# controller_A-rev_1.net
KiCad netlist of a schematic drawn in EAGLE
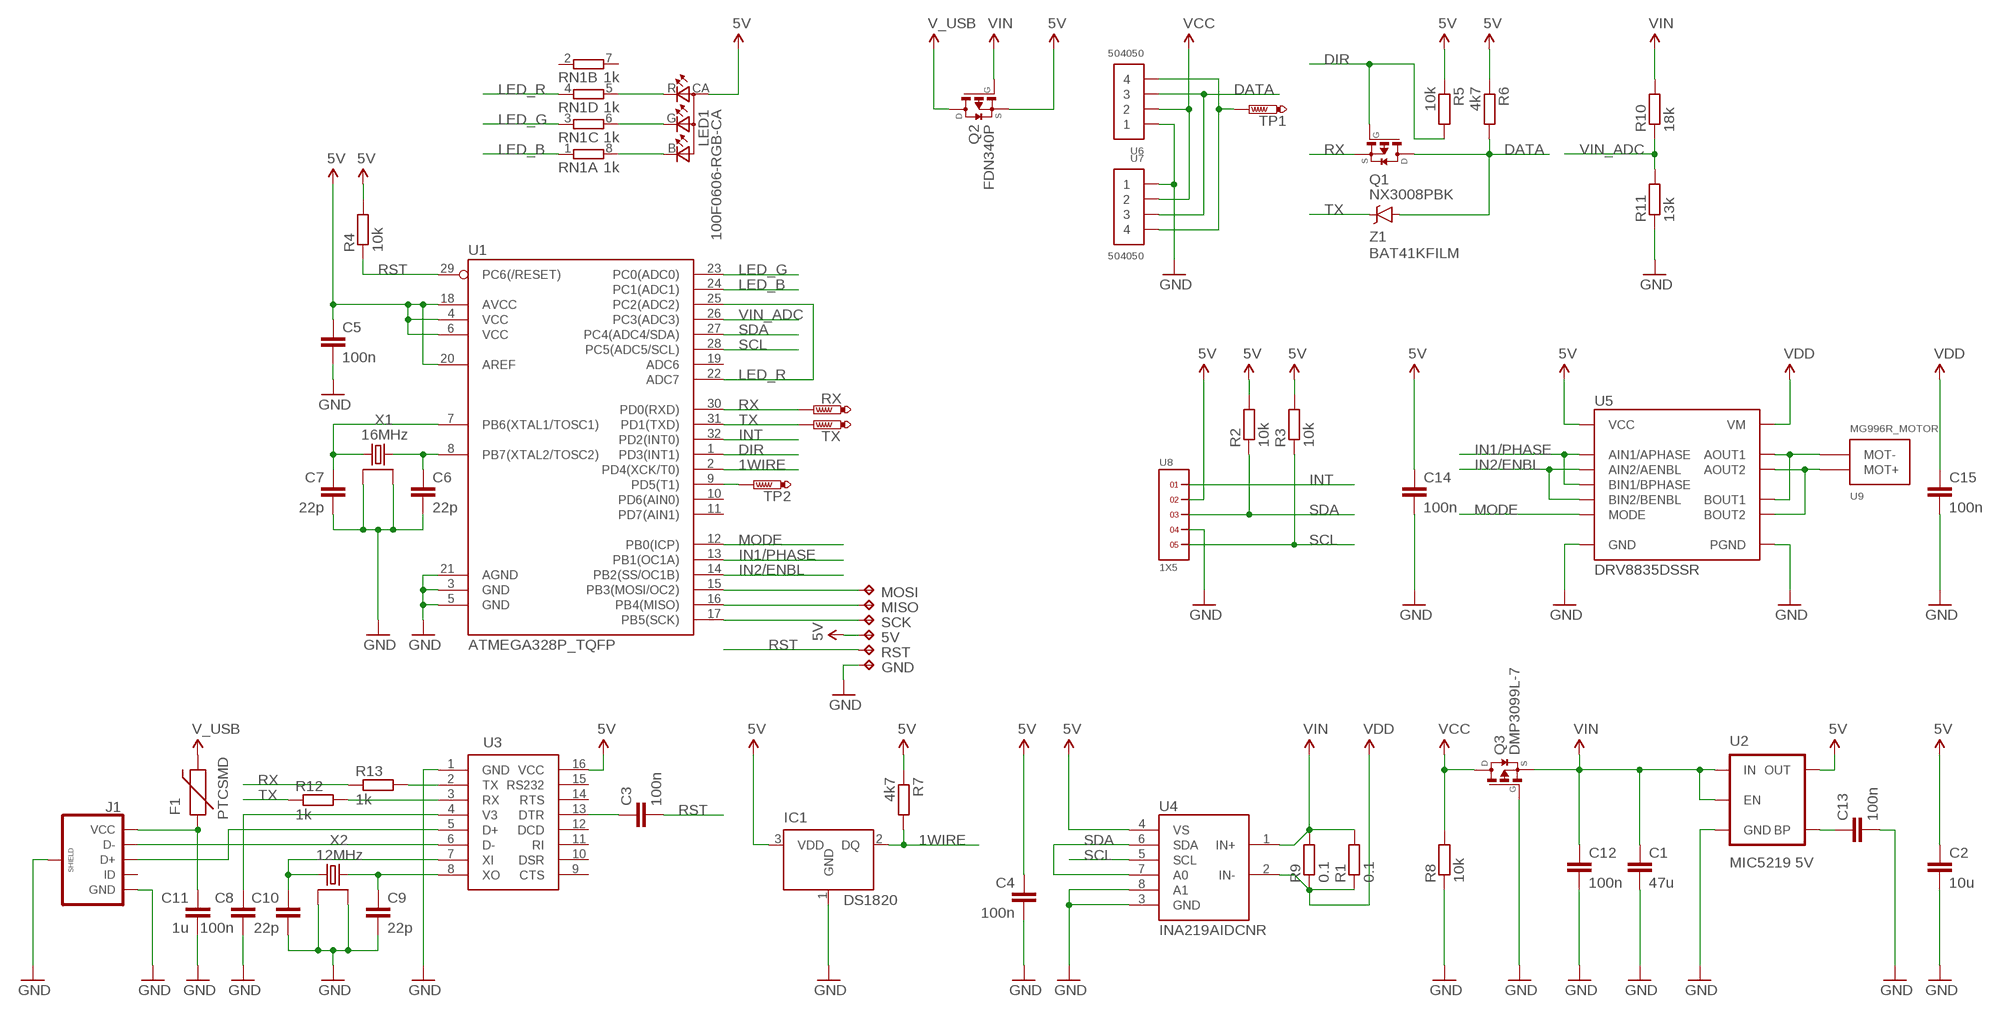
[diagram p0: schematic, sheet 1]

(export (version "E")
  (design (tool "Eeschema 10.0.6"))
  (components
    (comp (ref "5V")
      (value "TPTP07SQ")
      (footprint "eagle-import:TP07SQ")
      (libsource (lib "eagle-import") (part "TPTP07SQ"))
    )
    (comp (ref "C1")
      (value "47u")
      (footprint "eagle-import:C1206")
      (libsource (lib "eagle-import") (part "C-EUC1206"))
    )
    (comp (ref "C2")
      (value "10u")
      (footprint "eagle-import:C0603K")
      (libsource (lib "eagle-import") (part "C-EUC0603K"))
    )
    (comp (ref "C3")
      (value "100n")
      (footprint "eagle-import:C0402K")
      (libsource (lib "eagle-import") (part "C-EUC0402K"))
    )
    (comp (ref "C4")
      (value "100n")
      (footprint "eagle-import:C0402K")
      (libsource (lib "eagle-import") (part "C-EUC0402K"))
    )
    (comp (ref "C5")
      (value "100n")
      (footprint "eagle-import:C0402K")
      (libsource (lib "eagle-import") (part "C-EUC0402K"))
    )
    (comp (ref "C6")
      (value "22p")
      (footprint "eagle-import:C0402K")
      (libsource (lib "eagle-import") (part "C-EUC0402K"))
    )
    (comp (ref "C7")
      (value "22p")
      (footprint "eagle-import:C0402K")
      (libsource (lib "eagle-import") (part "C-EUC0402K"))
    )
    (comp (ref "C8")
      (value "100n")
      (footprint "eagle-import:C0402K")
      (libsource (lib "eagle-import") (part "C-EUC0402K"))
    )
    (comp (ref "C9")
      (value "22p")
      (footprint "eagle-import:C0402K")
      (libsource (lib "eagle-import") (part "C-EUC0402K"))
    )
    (comp (ref "C10")
      (value "22p")
      (footprint "eagle-import:C0402K")
      (libsource (lib "eagle-import") (part "C-EUC0402K"))
    )
    (comp (ref "C11")
      (value "1u")
      (footprint "eagle-import:C0402K")
      (libsource (lib "eagle-import") (part "C-EUC0402K"))
    )
    (comp (ref "C12")
      (value "100n")
      (footprint "eagle-import:C0402K")
      (libsource (lib "eagle-import") (part "C-EUC0402K"))
    )
    (comp (ref "C13")
      (value "100n")
      (footprint "eagle-import:C0402K")
      (libsource (lib "eagle-import") (part "C-EUC0402K"))
    )
    (comp (ref "C14")
      (value "100n")
      (footprint "eagle-import:C0402K")
      (libsource (lib "eagle-import") (part "C-EUC0402K"))
    )
    (comp (ref "C15")
      (value "100n")
      (footprint "eagle-import:C0402K")
      (libsource (lib "eagle-import") (part "C-EUC0402K"))
    )
    (comp (ref "F1")
      (value "PTCSMD")
      (footprint "eagle-import:PTC-1206")
      (libsource (lib "eagle-import") (part "PTCSMD"))
    )
    (comp (ref "GND")
      (value "TPTP07SQ")
      (footprint "eagle-import:TP07SQ")
      (libsource (lib "eagle-import") (part "TPTP07SQ"))
    )
    (comp (ref "IC1")
      (value "DS1820")
      (footprint "eagle-import:TO-92")
      (libsource (lib "eagle-import") (part "DS1820"))
    )
    (comp (ref "J1")
      (value "USB_MICROB_PLUGCONN-11752")
      (footprint "eagle-import:USB-B-MICRO-SMD_V03")
      (libsource (lib "eagle-import") (part "USB_MICROB_PLUGCONN-11752"))
    )
    (comp (ref "LED1")
      (value "100F0606-RGB-CA")
      (footprint "eagle-import:1616")
      (libsource (lib "eagle-import") (part "100F0606-RGB-CA"))
    )
    (comp (ref "MISO")
      (value "TPTP07SQ")
      (footprint "eagle-import:TP07SQ")
      (libsource (lib "eagle-import") (part "TPTP07SQ"))
    )
    (comp (ref "MOSI")
      (value "TPTP07SQ")
      (footprint "eagle-import:TP07SQ")
      (libsource (lib "eagle-import") (part "TPTP07SQ"))
    )
    (comp (ref "Q1")
      (value "NX3008PBK")
      (footprint "eagle-import:SSOT-3")
      (libsource (lib "eagle-import") (part "FDN340P"))
    )
    (comp (ref "Q2")
      (value "FDN340P")
      (footprint "eagle-import:SSOT-3")
      (libsource (lib "eagle-import") (part "FDN340P"))
    )
    (comp (ref "Q3")
      (value "DMP3099L-7")
      (footprint "eagle-import:SOT23")
      (libsource (lib "eagle-import") (part "SI2333DS"))
    )
    (comp (ref "R1")
      (value "0.1")
      (footprint "eagle-import:R0603")
      (libsource (lib "eagle-import") (part "R-EU_R0603"))
    )
    (comp (ref "R2")
      (value "10k")
      (footprint "eagle-import:R0402")
      (libsource (lib "eagle-import") (part "R-EU_R0402"))
    )
    (comp (ref "R3")
      (value "10k")
      (footprint "eagle-import:R0402")
      (libsource (lib "eagle-import") (part "R-EU_R0402"))
    )
    (comp (ref "R4")
      (value "10k")
      (footprint "eagle-import:R0402")
      (libsource (lib "eagle-import") (part "R-EU_R0402"))
    )
    (comp (ref "R5")
      (value "10k")
      (footprint "eagle-import:R0402")
      (libsource (lib "eagle-import") (part "R-EU_R0402"))
    )
    (comp (ref "R6")
      (value "4k7")
      (footprint "eagle-import:R0402")
      (libsource (lib "eagle-import") (part "R-EU_R0402"))
    )
    (comp (ref "R7")
      (value "4k7")
      (footprint "eagle-import:R0402")
      (libsource (lib "eagle-import") (part "R-EU_R0402"))
    )
    (comp (ref "R8")
      (value "10k")
      (footprint "eagle-import:R0402")
      (libsource (lib "eagle-import") (part "R-EU_R0402"))
    )
    (comp (ref "R9")
      (value "0.1")
      (footprint "eagle-import:R2512")
      (libsource (lib "eagle-import") (part "R-EU_R2512"))
    )
    (comp (ref "R10")
      (value "18k")
      (footprint "eagle-import:R0402")
      (libsource (lib "eagle-import") (part "R-EU_R0402"))
    )
    (comp (ref "R11")
      (value "13k")
      (footprint "eagle-import:R0402")
      (libsource (lib "eagle-import") (part "R-EU_R0402"))
    )
    (comp (ref "R12")
      (value "1k")
      (footprint "eagle-import:R0402")
      (libsource (lib "eagle-import") (part "R-EU_R0402"))
    )
    (comp (ref "R13")
      (value "1k")
      (footprint "eagle-import:R0402")
      (libsource (lib "eagle-import") (part "R-EU_R0402"))
    )
    (comp (ref "RN1")
      (value "1k")
      (footprint "eagle-import:YC124")
      (libsource (lib "eagle-import") (part "4R-NYC124"))
    )
    (comp (ref "RST")
      (value "TPTP07SQ")
      (footprint "eagle-import:TP07SQ")
      (libsource (lib "eagle-import") (part "TPTP07SQ"))
    )
    (comp (ref "RX")
      (value "PTR1TP10R")
      (footprint "eagle-import:TP10R")
      (libsource (lib "eagle-import") (part "PTR1TP10R"))
    )
    (comp (ref "SCK")
      (value "TPTP07SQ")
      (footprint "eagle-import:TP07SQ")
      (libsource (lib "eagle-import") (part "TPTP07SQ"))
    )
    (comp (ref "TP1")
      (value "PTR1TP10R")
      (footprint "eagle-import:TP10R")
      (libsource (lib "eagle-import") (part "PTR1TP10R"))
    )
    (comp (ref "TP2")
      (value "PTR1TP10R")
      (footprint "eagle-import:TP10R")
      (libsource (lib "eagle-import") (part "PTR1TP10R"))
    )
    (comp (ref "TX")
      (value "PTR1TP10R")
      (footprint "eagle-import:TP10R")
      (libsource (lib "eagle-import") (part "PTR1TP10R"))
    )
    (comp (ref "U1")
      (value "ATMEGA328P_TQFP")
      (footprint "eagle-import:TQFP32-08")
      (libsource (lib "eagle-import") (part "ATMEGA328P_TQFP"))
    )
    (comp (ref "U2")
      (value "MIC5219 5V")
      (footprint "eagle-import:SOT23-5")
      (libsource (lib "eagle-import") (part "V_REG_MIC52195V"))
    )
    (comp (ref "U3")
      (value "CH340G")
      (footprint "eagle-import:SOIC16")
      (libsource (lib "eagle-import") (part "CH340G"))
    )
    (comp (ref "U4")
      (value "INA219AIDCNR")
      (footprint "eagle-import:SOT23-8L")
      (libsource (lib "eagle-import") (part "INA219AIDCNR"))
    )
    (comp (ref "U5")
      (value "DRV8835DSSR")
      (footprint "eagle-import:WSON-12")
      (libsource (lib "eagle-import") (part "DRV8835DSSR"))
    )
    (comp (ref "U6")
      (value "504050")
      (footprint "eagle-import:504050")
      (libsource (lib "eagle-import") (part "504050"))
    )
    (comp (ref "U7")
      (value "504050")
      (footprint "eagle-import:504050")
      (libsource (lib "eagle-import") (part "504050"))
    )
    (comp (ref "U8")
      (value "1X5")
      (footprint "eagle-import:1X5")
      (libsource (lib "eagle-import") (part "1X5"))
    )
    (comp (ref "U9")
      (value "MG996R_MOTOR")
      (footprint "eagle-import:MOTOR")
      (libsource (lib "eagle-import") (part "MG996R_MOTOR"))
    )
    (comp (ref "X1")
      (value "16MHz")
      (footprint "eagle-import:OSC3225")
      (libsource (lib "eagle-import") (part "GSX-331"))
    )
    (comp (ref "X2")
      (value "12MHz")
      (footprint "eagle-import:OSC3225")
      (libsource (lib "eagle-import") (part "GSX-331"))
    )
    (comp (ref "Z1")
      (value "BAT41KFILM")
      (footprint "eagle-import:SOD-523")
      (libsource (lib "eagle-import") (part "BAT41KFILM"))
    )
  )
  (nets
    (net (code "1") (name "/1WIRE") (class "Default")
      (node (ref "IC1") (pin "2") (pinfunction "DQ_2") (pintype "output"))
      (node (ref "R7") (pin "2") (pinfunction "2_2") (pintype "passive"))
      (node (ref "U1") (pin "2") (pinfunction "PD4(XCK/T0)_2") (pintype "bidirectional"))
    )
    (net (code "2") (name "/DATA") (class "Default")
      (node (ref "Q1") (pin "3") (pinfunction "D_3") (pintype "passive"))
      (node (ref "R6") (pin "2") (pinfunction "2_2") (pintype "passive"))
      (node (ref "U6") (pin "P$3") (pinfunction "3_P$3") (pintype "bidirectional"))
      (node (ref "U7") (pin "P$3") (pinfunction "3_P$3") (pintype "bidirectional"))
      (node (ref "Z1") (pin "P$1") (pinfunction "1_P$1") (pintype "passive"))
    )
    (net (code "3") (name "/DIR") (class "Default")
      (node (ref "Q1") (pin "1") (pinfunction "G_1") (pintype "passive"))
      (node (ref "R5") (pin "2") (pinfunction "2_2") (pintype "passive"))
      (node (ref "U1") (pin "1") (pinfunction "PD3(INT1)_1") (pintype "bidirectional"))
    )
    (net (code "4") (name "/IN1{slash}PHASE") (class "Default")
      (node (ref "U1") (pin "13") (pinfunction "PB1(OC1A)_13") (pintype "bidirectional"))
      (node (ref "U5") (pin "P$10") (pinfunction "AIN1/APHASE_P$10") (pintype "bidirectional"))
      (node (ref "U5") (pin "P$8") (pinfunction "BIN1/BPHASE_P$8") (pintype "bidirectional"))
    )
    (net (code "5") (name "/IN2{slash}ENBL") (class "Default")
      (node (ref "U1") (pin "14") (pinfunction "PB2(SS/OC1B)_14") (pintype "bidirectional"))
      (node (ref "U5") (pin "P$7") (pinfunction "BIN2/BENBL_P$7") (pintype "bidirectional"))
      (node (ref "U5") (pin "P$9") (pinfunction "AIN2/AENBL_P$9") (pintype "bidirectional"))
    )
    (net (code "6") (name "/INT") (class "Default")
      (node (ref "U1") (pin "32") (pinfunction "PD2(INT0)_32") (pintype "bidirectional"))
      (node (ref "U8") (pin "1") (pinfunction "1_1") (pintype "bidirectional"))
    )
    (net (code "7") (name "/LED_B") (class "Default")
      (node (ref "RN1") (pin "1") (pinfunction "1_1") (pintype "passive"))
      (node (ref "U1") (pin "24") (pinfunction "PC1(ADC1)_24") (pintype "bidirectional"))
    )
    (net (code "8") (name "/LED_G") (class "Default")
      (node (ref "RN1") (pin "3") (pinfunction "1_3") (pintype "passive"))
      (node (ref "U1") (pin "23") (pinfunction "PC0(ADC0)_23") (pintype "bidirectional"))
    )
    (net (code "9") (name "/LED_R") (class "Default")
      (node (ref "RN1") (pin "4") (pinfunction "1_4") (pintype "passive"))
      (node (ref "U1") (pin "22") (pinfunction "ADC7_22") (pintype "bidirectional"))
      (node (ref "U1") (pin "25") (pinfunction "PC2(ADC2)_25") (pintype "bidirectional"))
    )
    (net (code "10") (name "/MODE") (class "Default")
      (node (ref "U1") (pin "12") (pinfunction "PB0(ICP)_12") (pintype "bidirectional"))
      (node (ref "U5") (pin "P$11") (pinfunction "MODE_P$11") (pintype "bidirectional"))
    )
    (net (code "11") (name "/RST") (class "Default")
      (node (ref "C3") (pin "2") (pinfunction "2_2") (pintype "passive"))
      (node (ref "R4") (pin "1") (pinfunction "1_1") (pintype "passive"))
      (node (ref "RST") (pin "TP") (pinfunction "TP_TP") (pintype "input"))
      (node (ref "U1") (pin "29") (pinfunction "PC6(/RESET)_29") (pintype "bidirectional"))
    )
    (net (code "12") (name "/RX") (class "Default")
      (node (ref "Q1") (pin "2") (pinfunction "S_2") (pintype "passive"))
      (node (ref "R13") (pin "1") (pinfunction "1_1") (pintype "passive"))
      (node (ref "RX") (pin "TP") (pinfunction "TP_TP") (pintype "input"))
      (node (ref "U1") (pin "30") (pinfunction "PD0(RXD)_30") (pintype "bidirectional"))
    )
    (net (code "13") (name "/SCL") (class "Default")
      (node (ref "R3") (pin "1") (pinfunction "1_1") (pintype "passive"))
      (node (ref "U1") (pin "28") (pinfunction "PC5(ADC5/SCL)_28") (pintype "bidirectional"))
      (node (ref "U4") (pin "5") (pinfunction "SCL_5") (pintype "bidirectional"))
      (node (ref "U8") (pin "5") (pinfunction "5_5") (pintype "bidirectional"))
    )
    (net (code "14") (name "/SDA") (class "Default")
      (node (ref "R2") (pin "1") (pinfunction "1_1") (pintype "passive"))
      (node (ref "U1") (pin "27") (pinfunction "PC4(ADC4/SDA)_27") (pintype "bidirectional"))
      (node (ref "U4") (pin "6") (pinfunction "SDA_6") (pintype "bidirectional"))
      (node (ref "U4") (pin "7") (pinfunction "A0_7") (pintype "input"))
      (node (ref "U8") (pin "3") (pinfunction "3_3") (pintype "bidirectional"))
    )
    (net (code "15") (name "/TX") (class "Default")
      (node (ref "R12") (pin "1") (pinfunction "1_1") (pintype "passive"))
      (node (ref "TX") (pin "TP") (pinfunction "TP_TP") (pintype "input"))
      (node (ref "U1") (pin "31") (pinfunction "PD1(TXD)_31") (pintype "bidirectional"))
      (node (ref "Z1") (pin "P$2") (pinfunction "2_P$2") (pintype "passive"))
    )
    (net (code "16") (name "/VIN_ADC") (class "Default")
      (node (ref "R10") (pin "1") (pinfunction "1_1") (pintype "passive"))
      (node (ref "R11") (pin "2") (pinfunction "2_2") (pintype "passive"))
      (node (ref "U1") (pin "26") (pinfunction "PC3(ADC3)_26") (pintype "bidirectional"))
    )
    (net (code "17") (name "5V") (class "Default")
      (node (ref "5V") (pin "TP") (pinfunction "TP_TP") (pintype "input"))
      (node (ref "C14") (pin "1") (pinfunction "1_1") (pintype "passive"))
      (node (ref "C2") (pin "1") (pinfunction "1_1") (pintype "passive"))
      (node (ref "C4") (pin "1") (pinfunction "1_1") (pintype "passive"))
      (node (ref "C5") (pin "1") (pinfunction "1_1") (pintype "passive"))
      (node (ref "IC1") (pin "3") (pinfunction "VDD_3") (pintype "input"))
      (node (ref "LED1") (pin "CA") (pinfunction "CA_CA") (pintype "passive"))
      (node (ref "Q2") (pin "2") (pinfunction "S_2") (pintype "passive"))
      (node (ref "R2") (pin "2") (pinfunction "2_2") (pintype "passive"))
      (node (ref "R3") (pin "2") (pinfunction "2_2") (pintype "passive"))
      (node (ref "R4") (pin "2") (pinfunction "2_2") (pintype "passive"))
      (node (ref "R5") (pin "1") (pinfunction "1_1") (pintype "passive"))
      (node (ref "R6") (pin "1") (pinfunction "1_1") (pintype "passive"))
      (node (ref "R7") (pin "1") (pinfunction "1_1") (pintype "passive"))
      (node (ref "U1") (pin "18") (pinfunction "AVCC_18") (pintype "bidirectional"))
      (node (ref "U1") (pin "20") (pinfunction "AREF_20") (pintype "bidirectional"))
      (node (ref "U1") (pin "4") (pinfunction "VCC_4") (pintype "bidirectional"))
      (node (ref "U1") (pin "6") (pinfunction "VCC_6") (pintype "bidirectional"))
      (node (ref "U2") (pin "5") (pinfunction "OUT_5") (pintype "passive"))
      (node (ref "U3") (pin "16") (pinfunction "VCC_16") (pintype "bidirectional"))
      (node (ref "U4") (pin "4") (pinfunction "VS_4") (pintype "power_in"))
      (node (ref "U5") (pin "P$12") (pinfunction "VCC_P$12") (pintype "bidirectional"))
      (node (ref "U8") (pin "2") (pinfunction "2_2") (pintype "bidirectional"))
    )
    (net (code "18") (name "GND") (class "Default")
      (node (ref "C1") (pin "2") (pinfunction "2_2") (pintype "passive"))
      (node (ref "C10") (pin "2") (pinfunction "2_2") (pintype "passive"))
      (node (ref "C11") (pin "2") (pinfunction "2_2") (pintype "passive"))
      (node (ref "C12") (pin "2") (pinfunction "2_2") (pintype "passive"))
      (node (ref "C13") (pin "2") (pinfunction "2_2") (pintype "passive"))
      (node (ref "C14") (pin "2") (pinfunction "2_2") (pintype "passive"))
      (node (ref "C15") (pin "2") (pinfunction "2_2") (pintype "passive"))
      (node (ref "C2") (pin "2") (pinfunction "2_2") (pintype "passive"))
      (node (ref "C4") (pin "2") (pinfunction "2_2") (pintype "passive"))
      (node (ref "C5") (pin "2") (pinfunction "2_2") (pintype "passive"))
      (node (ref "C6") (pin "2") (pinfunction "2_2") (pintype "passive"))
      (node (ref "C7") (pin "2") (pinfunction "2_2") (pintype "passive"))
      (node (ref "C8") (pin "2") (pinfunction "2_2") (pintype "passive"))
      (node (ref "C9") (pin "2") (pinfunction "2_2") (pintype "passive"))
      (node (ref "GND") (pin "TP") (pinfunction "TP_TP") (pintype "input"))
      (node (ref "IC1") (pin "1") (pinfunction "GND_1") (pintype "power_in"))
      (node (ref "J1") (pin "GND") (pinfunction "GND_GND") (pintype "bidirectional"))
      (node (ref "J1") (pin "SHIELD1") (pinfunction "SHIELD_SHIELD1") (pintype "bidirectional"))
      (node (ref "J1") (pin "SHIELD2") (pinfunction "SHIELD_SHIELD2") (pintype "bidirectional"))
      (node (ref "J1") (pin "SHIELD3") (pinfunction "SHIELD_SHIELD3") (pintype "bidirectional"))
      (node (ref "Q3") (pin "1") (pinfunction "G_1") (pintype "passive"))
      (node (ref "R11") (pin "1") (pinfunction "1_1") (pintype "passive"))
      (node (ref "R8") (pin "1") (pinfunction "1_1") (pintype "passive"))
      (node (ref "U1") (pin "21") (pinfunction "AGND_21") (pintype "bidirectional"))
      (node (ref "U1") (pin "3") (pinfunction "GND_3") (pintype "bidirectional"))
      (node (ref "U1") (pin "5") (pinfunction "GND_5") (pintype "bidirectional"))
      (node (ref "U2") (pin "2") (pinfunction "GND_2") (pintype "input"))
      (node (ref "U3") (pin "1") (pinfunction "GND_1") (pintype "bidirectional"))
      (node (ref "U4") (pin "3") (pinfunction "GND_3") (pintype "power_in"))
      (node (ref "U4") (pin "8") (pinfunction "A1_8") (pintype "input"))
      (node (ref "U5") (pin "P$13") (pinfunction "PGND_P$13") (pintype "bidirectional"))
      (node (ref "U5") (pin "P$14") (pinfunction "PGND_P$14") (pintype "bidirectional"))
      (node (ref "U5") (pin "P$15") (pinfunction "PGND_P$15") (pintype "bidirectional"))
      (node (ref "U5") (pin "P$16") (pinfunction "PGND_P$16") (pintype "bidirectional"))
      (node (ref "U5") (pin "P$6") (pinfunction "GND_P$6") (pintype "bidirectional"))
      (node (ref "U6") (pin "P$1") (pinfunction "1_P$1") (pintype "bidirectional"))
      (node (ref "U7") (pin "P$1") (pinfunction "1_P$1") (pintype "bidirectional"))
      (node (ref "U8") (pin "4") (pinfunction "4_4") (pintype "bidirectional"))
      (node (ref "X1") (pin "P$2") (pinfunction "2_P$2") (pintype "passive"))
      (node (ref "X1") (pin "P$4") (pinfunction "4_P$4") (pintype "passive"))
      (node (ref "X2") (pin "P$2") (pinfunction "2_P$2") (pintype "passive"))
      (node (ref "X2") (pin "P$4") (pinfunction "4_P$4") (pintype "passive"))
    )
    (net (code "19") (name "Net-(J1-VCC)") (class "Default")
      (node (ref "C11") (pin "1") (pinfunction "1_1") (pintype "passive"))
      (node (ref "F1") (pin "1") (pinfunction "1_1") (pintype "bidirectional"))
      (node (ref "J1") (pin "VBUS") (pinfunction "VCC_VBUS") (pintype "bidirectional"))
    )
    (net (code "20") (name "Net-(RN1A-2)") (class "Default")
      (node (ref "LED1") (pin "B") (pinfunction "B_B") (pintype "passive"))
      (node (ref "RN1") (pin "8") (pinfunction "2_8") (pintype "passive"))
    )
    (net (code "21") (name "Net-(RN1C-2)") (class "Default")
      (node (ref "LED1") (pin "G") (pinfunction "G_G") (pintype "passive"))
      (node (ref "RN1") (pin "6") (pinfunction "2_6") (pintype "passive"))
    )
    (net (code "22") (name "Net-(RN1D-2)") (class "Default")
      (node (ref "LED1") (pin "R") (pinfunction "R_R") (pintype "passive"))
      (node (ref "RN1") (pin "5") (pinfunction "2_5") (pintype "passive"))
    )
    (net (code "23") (name "Net-(U1-PB3(MOSI{slash}OC2))") (class "Default")
      (node (ref "MOSI") (pin "TP") (pinfunction "TP_TP") (pintype "input"))
      (node (ref "U1") (pin "15") (pinfunction "PB3(MOSI/OC2)_15") (pintype "bidirectional"))
    )
    (net (code "24") (name "Net-(U1-PB4(MISO))") (class "Default")
      (node (ref "MISO") (pin "TP") (pinfunction "TP_TP") (pintype "input"))
      (node (ref "U1") (pin "16") (pinfunction "PB4(MISO)_16") (pintype "bidirectional"))
    )
    (net (code "25") (name "Net-(U1-PB5(SCK))") (class "Default")
      (node (ref "SCK") (pin "TP") (pinfunction "TP_TP") (pintype "input"))
      (node (ref "U1") (pin "17") (pinfunction "PB5(SCK)_17") (pintype "bidirectional"))
    )
    (net (code "26") (name "Net-(U1-PB6(XTAL1{slash}TOSC1))") (class "Default")
      (node (ref "C7") (pin "1") (pinfunction "1_1") (pintype "passive"))
      (node (ref "U1") (pin "7") (pinfunction "PB6(XTAL1/TOSC1)_7") (pintype "bidirectional"))
      (node (ref "X1") (pin "P$3") (pinfunction "3_P$3") (pintype "passive"))
    )
    (net (code "27") (name "Net-(U1-PB7(XTAL2{slash}TOSC2))") (class "Default")
      (node (ref "C6") (pin "1") (pinfunction "1_1") (pintype "passive"))
      (node (ref "U1") (pin "8") (pinfunction "PB7(XTAL2/TOSC2)_8") (pintype "bidirectional"))
      (node (ref "X1") (pin "P$1") (pinfunction "1_P$1") (pintype "passive"))
    )
    (net (code "28") (name "Net-(U1-PD5(T1))") (class "Default")
      (node (ref "TP2") (pin "TP") (pinfunction "TP_TP") (pintype "input"))
      (node (ref "U1") (pin "9") (pinfunction "PD5(T1)_9") (pintype "bidirectional"))
    )
    (net (code "29") (name "Net-(U2-BP)") (class "Default")
      (node (ref "C13") (pin "1") (pinfunction "1_1") (pintype "passive"))
      (node (ref "U2") (pin "4") (pinfunction "BP_4") (pintype "input"))
    )
    (net (code "30") (name "Net-(U3-D+)") (class "Default")
      (node (ref "J1") (pin "D+") (pinfunction "D+_D+") (pintype "bidirectional"))
      (node (ref "U3") (pin "5") (pinfunction "D+_5") (pintype "bidirectional"))
    )
    (net (code "31") (name "Net-(U3-D-)") (class "Default")
      (node (ref "J1") (pin "D-") (pinfunction "D-_D-") (pintype "bidirectional"))
      (node (ref "U3") (pin "6") (pinfunction "D-_6") (pintype "bidirectional"))
    )
    (net (code "32") (name "Net-(U3-DTR)") (class "Default")
      (node (ref "C3") (pin "1") (pinfunction "1_1") (pintype "passive"))
      (node (ref "U3") (pin "13") (pinfunction "DTR_13") (pintype "bidirectional"))
    )
    (net (code "33") (name "Net-(U3-RX)") (class "Default")
      (node (ref "R12") (pin "2") (pinfunction "2_2") (pintype "passive"))
      (node (ref "U3") (pin "3") (pinfunction "RX_3") (pintype "bidirectional"))
    )
    (net (code "34") (name "Net-(U3-TX)") (class "Default")
      (node (ref "R13") (pin "2") (pinfunction "2_2") (pintype "passive"))
      (node (ref "U3") (pin "2") (pinfunction "TX_2") (pintype "bidirectional"))
    )
    (net (code "35") (name "Net-(U3-V3)") (class "Default")
      (node (ref "C8") (pin "1") (pinfunction "1_1") (pintype "passive"))
      (node (ref "U3") (pin "4") (pinfunction "V3_4") (pintype "bidirectional"))
    )
    (net (code "36") (name "Net-(U3-XI)") (class "Default")
      (node (ref "C10") (pin "1") (pinfunction "1_1") (pintype "passive"))
      (node (ref "U3") (pin "7") (pinfunction "XI_7") (pintype "bidirectional"))
      (node (ref "X2") (pin "P$3") (pinfunction "3_P$3") (pintype "passive"))
    )
    (net (code "37") (name "Net-(U3-XO)") (class "Default")
      (node (ref "C9") (pin "1") (pinfunction "1_1") (pintype "passive"))
      (node (ref "U3") (pin "8") (pinfunction "XO_8") (pintype "bidirectional"))
      (node (ref "X2") (pin "P$1") (pinfunction "1_P$1") (pintype "passive"))
    )
    (net (code "38") (name "Net-(U5-AOUT1)") (class "Default")
      (node (ref "U5") (pin "P$2") (pinfunction "AOUT1_P$2") (pintype "bidirectional"))
      (node (ref "U5") (pin "P$4") (pinfunction "BOUT1_P$4") (pintype "bidirectional"))
      (node (ref "U9") (pin "P$3") (pinfunction "MOT-_P$3") (pintype "bidirectional"))
      (node (ref "U9") (pin "P$4") (pinfunction "MOT-_P$4") (pintype "bidirectional"))
    )
    (net (code "39") (name "Net-(U5-AOUT2)") (class "Default")
      (node (ref "U5") (pin "P$3") (pinfunction "AOUT2_P$3") (pintype "bidirectional"))
      (node (ref "U5") (pin "P$5") (pinfunction "BOUT2_P$5") (pintype "bidirectional"))
      (node (ref "U9") (pin "P$1") (pinfunction "MOT+_P$1") (pintype "bidirectional"))
      (node (ref "U9") (pin "P$2") (pinfunction "MOT+_P$2") (pintype "bidirectional"))
    )
    (net (code "40") (name "Net-(U6-4)") (class "Default")
      (node (ref "TP1") (pin "TP") (pinfunction "TP_TP") (pintype "input"))
      (node (ref "U6") (pin "P$4") (pinfunction "4_P$4") (pintype "bidirectional"))
      (node (ref "U7") (pin "P$4") (pinfunction "4_P$4") (pintype "bidirectional"))
    )
    (net (code "41") (name "VCC") (class "Default")
      (node (ref "Q3") (pin "3") (pinfunction "D_3") (pintype "passive"))
      (node (ref "R8") (pin "2") (pinfunction "2_2") (pintype "passive"))
      (node (ref "U6") (pin "P$2") (pinfunction "2_P$2") (pintype "bidirectional"))
      (node (ref "U7") (pin "P$2") (pinfunction "2_P$2") (pintype "bidirectional"))
    )
    (net (code "42") (name "VDD") (class "Default")
      (node (ref "C15") (pin "1") (pinfunction "1_1") (pintype "passive"))
      (node (ref "R1") (pin "1") (pinfunction "1_1") (pintype "passive"))
      (node (ref "R9") (pin "1") (pinfunction "1_1") (pintype "passive"))
      (node (ref "U4") (pin "2") (pinfunction "IN-_2") (pintype "input"))
      (node (ref "U5") (pin "P$1") (pinfunction "VM_P$1") (pintype "bidirectional"))
    )
    (net (code "43") (name "VIN") (class "Default")
      (node (ref "C1") (pin "1") (pinfunction "1_1") (pintype "passive"))
      (node (ref "C12") (pin "1") (pinfunction "1_1") (pintype "passive"))
      (node (ref "Q2") (pin "1") (pinfunction "G_1") (pintype "passive"))
      (node (ref "Q3") (pin "2") (pinfunction "S_2") (pintype "passive"))
      (node (ref "R1") (pin "2") (pinfunction "2_2") (pintype "passive"))
      (node (ref "R10") (pin "2") (pinfunction "2_2") (pintype "passive"))
      (node (ref "R9") (pin "2") (pinfunction "2_2") (pintype "passive"))
      (node (ref "U2") (pin "1") (pinfunction "IN_1") (pintype "input"))
      (node (ref "U2") (pin "3") (pinfunction "EN_3") (pintype "input"))
      (node (ref "U4") (pin "1") (pinfunction "IN+_1") (pintype "input"))
    )
    (net (code "44") (name "V_USB") (class "Default")
      (node (ref "F1") (pin "2") (pinfunction "2_2") (pintype "bidirectional"))
      (node (ref "Q2") (pin "3") (pinfunction "D_3") (pintype "passive"))
    )
    (net (code "45") (name "unconnected-(J1-PadID)") (class "Default")
      (node (ref "J1") (pin "ID") (pinfunction "ID_ID") (pintype "bidirectional"))
    )
    (net (code "46") (name "unconnected-(RN1B-1-Pad2)") (class "Default")
      (node (ref "RN1") (pin "2") (pinfunction "1_2") (pintype "passive"))
    )
    (net (code "47") (name "unconnected-(RN1B-2-Pad7)") (class "Default")
      (node (ref "RN1") (pin "7") (pinfunction "2_7") (pintype "passive"))
    )
    (net (code "48") (name "unconnected-(U1-ADC6-Pad19)") (class "Default")
      (node (ref "U1") (pin "19") (pinfunction "ADC6_19") (pintype "bidirectional"))
    )
    (net (code "49") (name "unconnected-(U1-PD6(AIN0)-Pad10)") (class "Default")
      (node (ref "U1") (pin "10") (pinfunction "PD6(AIN0)_10") (pintype "bidirectional"))
    )
    (net (code "50") (name "unconnected-(U1-PD7(AIN1)-Pad11)") (class "Default")
      (node (ref "U1") (pin "11") (pinfunction "PD7(AIN1)_11") (pintype "bidirectional"))
    )
    (net (code "51") (name "unconnected-(U3-CTS-Pad9)") (class "Default")
      (node (ref "U3") (pin "9") (pinfunction "CTS_9") (pintype "bidirectional"))
    )
    (net (code "52") (name "unconnected-(U3-DCD-Pad12)") (class "Default")
      (node (ref "U3") (pin "12") (pinfunction "DCD_12") (pintype "bidirectional"))
    )
    (net (code "53") (name "unconnected-(U3-DSR-Pad10)") (class "Default")
      (node (ref "U3") (pin "10") (pinfunction "DSR_10") (pintype "bidirectional"))
    )
    (net (code "54") (name "unconnected-(U3-RI-Pad11)") (class "Default")
      (node (ref "U3") (pin "11") (pinfunction "RI_11") (pintype "bidirectional"))
    )
    (net (code "55") (name "unconnected-(U3-RS232-Pad15)") (class "Default")
      (node (ref "U3") (pin "15") (pinfunction "RS232_15") (pintype "bidirectional"))
    )
    (net (code "56") (name "unconnected-(U3-RTS-Pad14)") (class "Default")
      (node (ref "U3") (pin "14") (pinfunction "RTS_14") (pintype "bidirectional"))
    )
  )
)
